# breakout.net
KiCad netlist of a schematic drawn in EAGLE
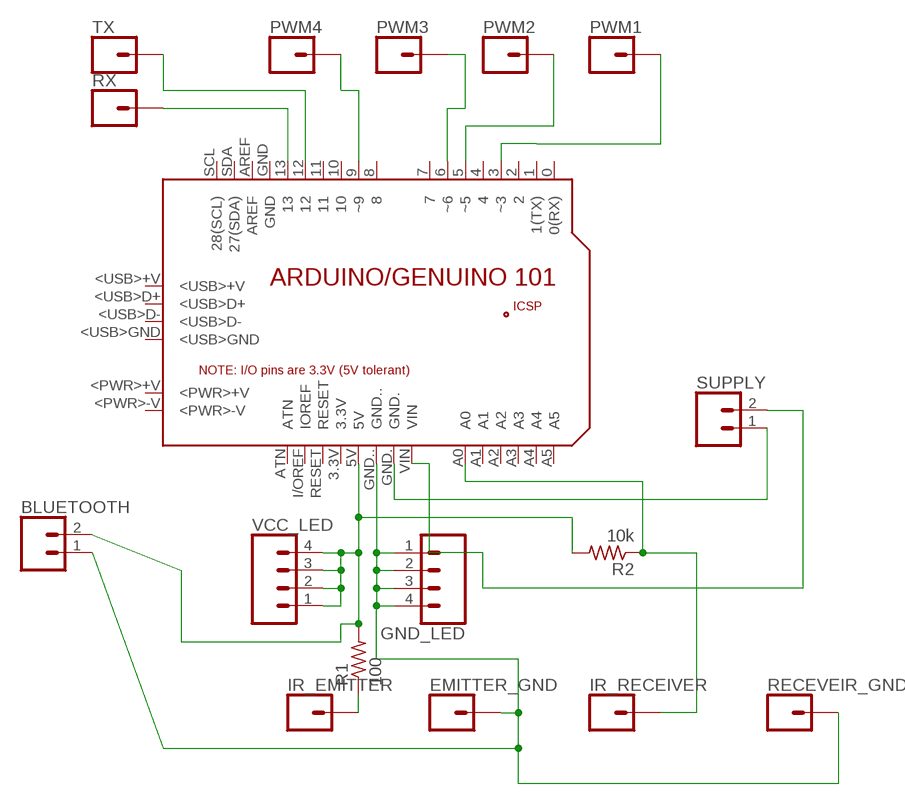
[diagram p0: schematic, sheet 1]

(export (version "E")
  (design (tool "Eeschema 10.0.6"))
  (components
    (comp (ref "BLUETOOTH")
      (value "CONN_02")
      (footprint "eagle-import:1X02")
      (libsource (lib "eagle-import") (part "CONN_02"))
    )
    (comp (ref "EMITTER_GND")
      (value "CONN_01")
      (footprint "eagle-import:1X01")
      (libsource (lib "eagle-import") (part "CONN_01"))
    )
    (comp (ref "GND_LED")
      (value "CONN_04")
      (footprint "eagle-import:1X04")
      (libsource (lib "eagle-import") (part "CONN_04"))
    )
    (comp (ref "IR_EMITTER")
      (value "CONN_01")
      (footprint "eagle-import:1X01")
      (libsource (lib "eagle-import") (part "CONN_01"))
    )
    (comp (ref "IR_RECEIVER")
      (value "CONN_01")
      (footprint "eagle-import:1X01")
      (libsource (lib "eagle-import") (part "CONN_01"))
    )
    (comp (ref "PCB1")
      (value "ARDUINO_101")
      (footprint "eagle-import:ARDUINO_101")
      (libsource (lib "eagle-import") (part "ARDUINO_101"))
    )
    (comp (ref "PWM1")
      (value "CONN_01")
      (footprint "eagle-import:1X01")
      (libsource (lib "eagle-import") (part "CONN_01"))
    )
    (comp (ref "PWM2")
      (value "CONN_01")
      (footprint "eagle-import:1X01")
      (libsource (lib "eagle-import") (part "CONN_01"))
    )
    (comp (ref "PWM3")
      (value "CONN_01")
      (footprint "eagle-import:1X01")
      (libsource (lib "eagle-import") (part "CONN_01"))
    )
    (comp (ref "PWM4")
      (value "CONN_01")
      (footprint "eagle-import:1X01")
      (libsource (lib "eagle-import") (part "CONN_01"))
    )
    (comp (ref "R1")
      (value "100")
      (footprint "eagle-import:R1206")
      (libsource (lib "eagle-import") (part "RES-US1206"))
    )
    (comp (ref "R2")
      (value "10k")
      (footprint "eagle-import:R1206")
      (libsource (lib "eagle-import") (part "RES-US1206"))
    )
    (comp (ref "RECEVEIR_GND")
      (value "CONN_01")
      (footprint "eagle-import:1X01")
      (libsource (lib "eagle-import") (part "CONN_01"))
    )
    (comp (ref "RX")
      (value "CONN_01")
      (footprint "eagle-import:1X01")
      (libsource (lib "eagle-import") (part "CONN_01"))
    )
    (comp (ref "SUPPLY")
      (value "CONN_02")
      (footprint "eagle-import:1X02")
      (libsource (lib "eagle-import") (part "CONN_02"))
    )
    (comp (ref "TX")
      (value "CONN_01")
      (footprint "eagle-import:1X01")
      (libsource (lib "eagle-import") (part "CONN_01"))
    )
    (comp (ref "VCC_LED")
      (value "CONN_04")
      (footprint "eagle-import:1X04")
      (libsource (lib "eagle-import") (part "CONN_04"))
    )
  )
  (nets
    (net (code "1") (name "Net-(BLUETOOTH-Pad1)") (class "Default")
      (node (ref "BLUETOOTH") (pin "1") (pinfunction "1_1") (pintype "passive"))
      (node (ref "EMITTER_GND") (pin "1") (pinfunction "1_1") (pintype "passive"))
      (node (ref "GND_LED") (pin "1") (pinfunction "1_1") (pintype "passive"))
      (node (ref "GND_LED") (pin "2") (pinfunction "2_2") (pintype "passive"))
      (node (ref "GND_LED") (pin "3") (pinfunction "3_3") (pintype "passive"))
      (node (ref "GND_LED") (pin "4") (pinfunction "4_4") (pintype "passive"))
      (node (ref "PCB1") (pin "GND..") (pinfunction "GND.._GND..") (pintype "bidirectional"))
      (node (ref "RECEVEIR_GND") (pin "1") (pinfunction "1_1") (pintype "passive"))
    )
    (net (code "2") (name "Net-(BLUETOOTH-Pad2)") (class "Default")
      (node (ref "BLUETOOTH") (pin "2") (pinfunction "2_2") (pintype "passive"))
      (node (ref "PCB1") (pin "5V") (pinfunction "5V_5V") (pintype "bidirectional"))
      (node (ref "R1") (pin "2") (pinfunction "2_2") (pintype "passive"))
      (node (ref "R2") (pin "2") (pinfunction "2_2") (pintype "passive"))
      (node (ref "VCC_LED") (pin "1") (pinfunction "1_1") (pintype "passive"))
      (node (ref "VCC_LED") (pin "2") (pinfunction "2_2") (pintype "passive"))
      (node (ref "VCC_LED") (pin "3") (pinfunction "3_3") (pintype "passive"))
      (node (ref "VCC_LED") (pin "4") (pinfunction "4_4") (pintype "passive"))
    )
    (net (code "3") (name "Net-(IR_EMITTER-Pad1)") (class "Default")
      (node (ref "IR_EMITTER") (pin "1") (pinfunction "1_1") (pintype "passive"))
      (node (ref "R1") (pin "1") (pinfunction "1_1") (pintype "passive"))
    )
    (net (code "4") (name "Net-(IR_RECEIVER-Pad1)") (class "Default")
      (node (ref "IR_RECEIVER") (pin "1") (pinfunction "1_1") (pintype "passive"))
      (node (ref "PCB1") (pin "A0") (pinfunction "A0_A0") (pintype "bidirectional"))
      (node (ref "R2") (pin "1") (pinfunction "1_1") (pintype "passive"))
    )
    (net (code "5") (name "Net-(PCB1-Pad12)") (class "Default")
      (node (ref "PCB1") (pin "12") (pinfunction "12_12") (pintype "bidirectional"))
      (node (ref "TX") (pin "1") (pinfunction "1_1") (pintype "passive"))
    )
    (net (code "6") (name "Net-(PCB1-Pad13)") (class "Default")
      (node (ref "PCB1") (pin "13") (pinfunction "13_13") (pintype "bidirectional"))
      (node (ref "RX") (pin "1") (pinfunction "1_1") (pintype "passive"))
    )
    (net (code "7") (name "Net-(PCB1-PadGND.)") (class "Default")
      (node (ref "PCB1") (pin "GND.") (pinfunction "GND._GND.") (pintype "bidirectional"))
      (node (ref "SUPPLY") (pin "1") (pinfunction "1_1") (pintype "passive"))
    )
    (net (code "8") (name "Net-(PCB1-PadVIN)") (class "Default")
      (node (ref "PCB1") (pin "VIN") (pinfunction "VIN_VIN") (pintype "bidirectional"))
      (node (ref "SUPPLY") (pin "2") (pinfunction "2_2") (pintype "passive"))
    )
    (net (code "9") (name "Net-(PCB1-~{3})") (class "Default")
      (node (ref "PCB1") (pin "3") (pinfunction "~{3}_3") (pintype "bidirectional"))
      (node (ref "PWM1") (pin "1") (pinfunction "1_1") (pintype "passive"))
    )
    (net (code "10") (name "Net-(PCB1-~{5})") (class "Default")
      (node (ref "PCB1") (pin "5") (pinfunction "~{5}_5") (pintype "bidirectional"))
      (node (ref "PWM2") (pin "1") (pinfunction "1_1") (pintype "passive"))
    )
    (net (code "11") (name "Net-(PCB1-~{6})") (class "Default")
      (node (ref "PCB1") (pin "6") (pinfunction "~{6}_6") (pintype "bidirectional"))
      (node (ref "PWM3") (pin "1") (pinfunction "1_1") (pintype "passive"))
    )
    (net (code "12") (name "Net-(PCB1-~{9})") (class "Default")
      (node (ref "PCB1") (pin "9") (pinfunction "~{9}_9") (pintype "bidirectional"))
      (node (ref "PWM4") (pin "1") (pinfunction "1_1") (pintype "passive"))
    )
    (net (code "13") (name "unconnected-(PCB1-0(RX)-Pad0)") (class "Default")
      (node (ref "PCB1") (pin "0") (pinfunction "0(RX)_0") (pintype "bidirectional"))
    )
    (net (code "14") (name "unconnected-(PCB1-1(TX)-Pad1)") (class "Default")
      (node (ref "PCB1") (pin "1") (pinfunction "1(TX)_1") (pintype "bidirectional"))
    )
    (net (code "15") (name "unconnected-(PCB1-27(SDA)-PadSDA)") (class "Default")
      (node (ref "PCB1") (pin "SDA") (pinfunction "27(SDA)_SDA") (pintype "bidirectional"))
    )
    (net (code "16") (name "unconnected-(PCB1-28(SCL)-PadSCL)") (class "Default")
      (node (ref "PCB1") (pin "SCL") (pinfunction "28(SCL)_SCL") (pintype "bidirectional"))
    )
    (net (code "17") (name "unconnected-(PCB1-IOREF-PadI{slash}OREF)") (class "Default")
      (node (ref "PCB1") (pin "I/OREF") (pinfunction "IOREF_I/OREF") (pintype "bidirectional"))
    )
    (net (code "18") (name "unconnected-(PCB1-Pad+5V)") (class "Default")
      (node (ref "PCB1") (pin "+5V") (pinfunction "+5V_+5V") (pintype "bidirectional"))
    )
    (net (code "19") (name "unconnected-(PCB1-Pad2)") (class "Default")
      (node (ref "PCB1") (pin "2") (pinfunction "2_2") (pintype "bidirectional"))
    )
    (net (code "20") (name "unconnected-(PCB1-Pad3.3V)") (class "Default")
      (node (ref "PCB1") (pin "3.3V") (pinfunction "3.3V_3.3V") (pintype "bidirectional"))
    )
    (net (code "21") (name "unconnected-(PCB1-Pad4)") (class "Default")
      (node (ref "PCB1") (pin "4") (pinfunction "4_4") (pintype "bidirectional"))
    )
    (net (code "22") (name "unconnected-(PCB1-Pad7)") (class "Default")
      (node (ref "PCB1") (pin "7") (pinfunction "7_7") (pintype "bidirectional"))
    )
    (net (code "23") (name "unconnected-(PCB1-Pad8)") (class "Default")
      (node (ref "PCB1") (pin "8") (pinfunction "8_8") (pintype "bidirectional"))
    )
    (net (code "24") (name "unconnected-(PCB1-Pad10)") (class "Default")
      (node (ref "PCB1") (pin "10") (pinfunction "10_10") (pintype "bidirectional"))
    )
    (net (code "25") (name "unconnected-(PCB1-Pad11)") (class "Default")
      (node (ref "PCB1") (pin "11") (pinfunction "11_11") (pintype "bidirectional"))
    )
    (net (code "26") (name "unconnected-(PCB1-Pad<PWR>+V)") (class "Default")
      (node (ref "PCB1") (pin "<PWR>+V") (pinfunction "<PWR>+V_<PWR>+V") (pintype "bidirectional"))
    )
    (net (code "27") (name "unconnected-(PCB1-Pad<PWR>-V)") (class "Default")
      (node (ref "PCB1") (pin "<PWR>-V") (pinfunction "<PWR>-V_<PWR>-V") (pintype "bidirectional"))
    )
    (net (code "28") (name "unconnected-(PCB1-Pad<USB>+V)") (class "Default")
      (node (ref "PCB1") (pin "<USB>+V") (pinfunction "<USB>+V_<USB>+V") (pintype "bidirectional"))
    )
    (net (code "29") (name "unconnected-(PCB1-Pad<USB>D+)") (class "Default")
      (node (ref "PCB1") (pin "<USB>D+") (pinfunction "<USB>D+_<USB>D+") (pintype "bidirectional"))
    )
    (net (code "30") (name "unconnected-(PCB1-Pad<USB>D-)") (class "Default")
      (node (ref "PCB1") (pin "<USB>D-") (pinfunction "<USB>D-_<USB>D-") (pintype "bidirectional"))
    )
    (net (code "31") (name "unconnected-(PCB1-Pad<USB>GND)") (class "Default")
      (node (ref "PCB1") (pin "<USB>GND") (pinfunction "<USB>GND_<USB>GND") (pintype "bidirectional"))
    )
    (net (code "32") (name "unconnected-(PCB1-PadA1)") (class "Default")
      (node (ref "PCB1") (pin "A1") (pinfunction "A1_A1") (pintype "bidirectional"))
    )
    (net (code "33") (name "unconnected-(PCB1-PadA2)") (class "Default")
      (node (ref "PCB1") (pin "A2") (pinfunction "A2_A2") (pintype "bidirectional"))
    )
    (net (code "34") (name "unconnected-(PCB1-PadA3)") (class "Default")
      (node (ref "PCB1") (pin "A3") (pinfunction "A3_A3") (pintype "bidirectional"))
    )
    (net (code "35") (name "unconnected-(PCB1-PadA4)") (class "Default")
      (node (ref "PCB1") (pin "A4") (pinfunction "A4_A4") (pintype "bidirectional"))
    )
    (net (code "36") (name "unconnected-(PCB1-PadA5)") (class "Default")
      (node (ref "PCB1") (pin "A5") (pinfunction "A5_A5") (pintype "bidirectional"))
    )
    (net (code "37") (name "unconnected-(PCB1-PadAREF)") (class "Default")
      (node (ref "PCB1") (pin "AREF") (pinfunction "AREF_AREF") (pintype "bidirectional"))
    )
    (net (code "38") (name "unconnected-(PCB1-PadATN)") (class "Default")
      (node (ref "PCB1") (pin "ATN") (pinfunction "ATN_ATN") (pintype "bidirectional"))
    )
    (net (code "39") (name "unconnected-(PCB1-PadGND)") (class "Default")
      (node (ref "PCB1") (pin "GND") (pinfunction "GND_GND") (pintype "bidirectional"))
    )
    (net (code "40") (name "unconnected-(PCB1-PadGND_)") (class "Default")
      (node (ref "PCB1") (pin "GND_") (pinfunction "GND__GND_") (pintype "bidirectional"))
    )
    (net (code "41") (name "unconnected-(PCB1-PadMISO)") (class "Default")
      (node (ref "PCB1") (pin "MISO") (pinfunction "MISO_MISO") (pintype "bidirectional"))
    )
    (net (code "42") (name "unconnected-(PCB1-PadMOSI)") (class "Default")
      (node (ref "PCB1") (pin "MOSI") (pinfunction "MOSI_MOSI") (pintype "bidirectional"))
    )
    (net (code "43") (name "unconnected-(PCB1-PadRESET)") (class "Default")
      (node (ref "PCB1") (pin "RESET") (pinfunction "RESET_RESET") (pintype "bidirectional"))
    )
    (net (code "44") (name "unconnected-(PCB1-PadRESET.)") (class "Default")
      (node (ref "PCB1") (pin "RESET.") (pinfunction "RESET._RESET.") (pintype "bidirectional"))
    )
    (net (code "45") (name "unconnected-(PCB1-PadSCK)") (class "Default")
      (node (ref "PCB1") (pin "SCK") (pinfunction "SCK_SCK") (pintype "bidirectional"))
    )
  )
)
